# LEDs.net
KiCad netlist of a schematic drawn in Altium Designer
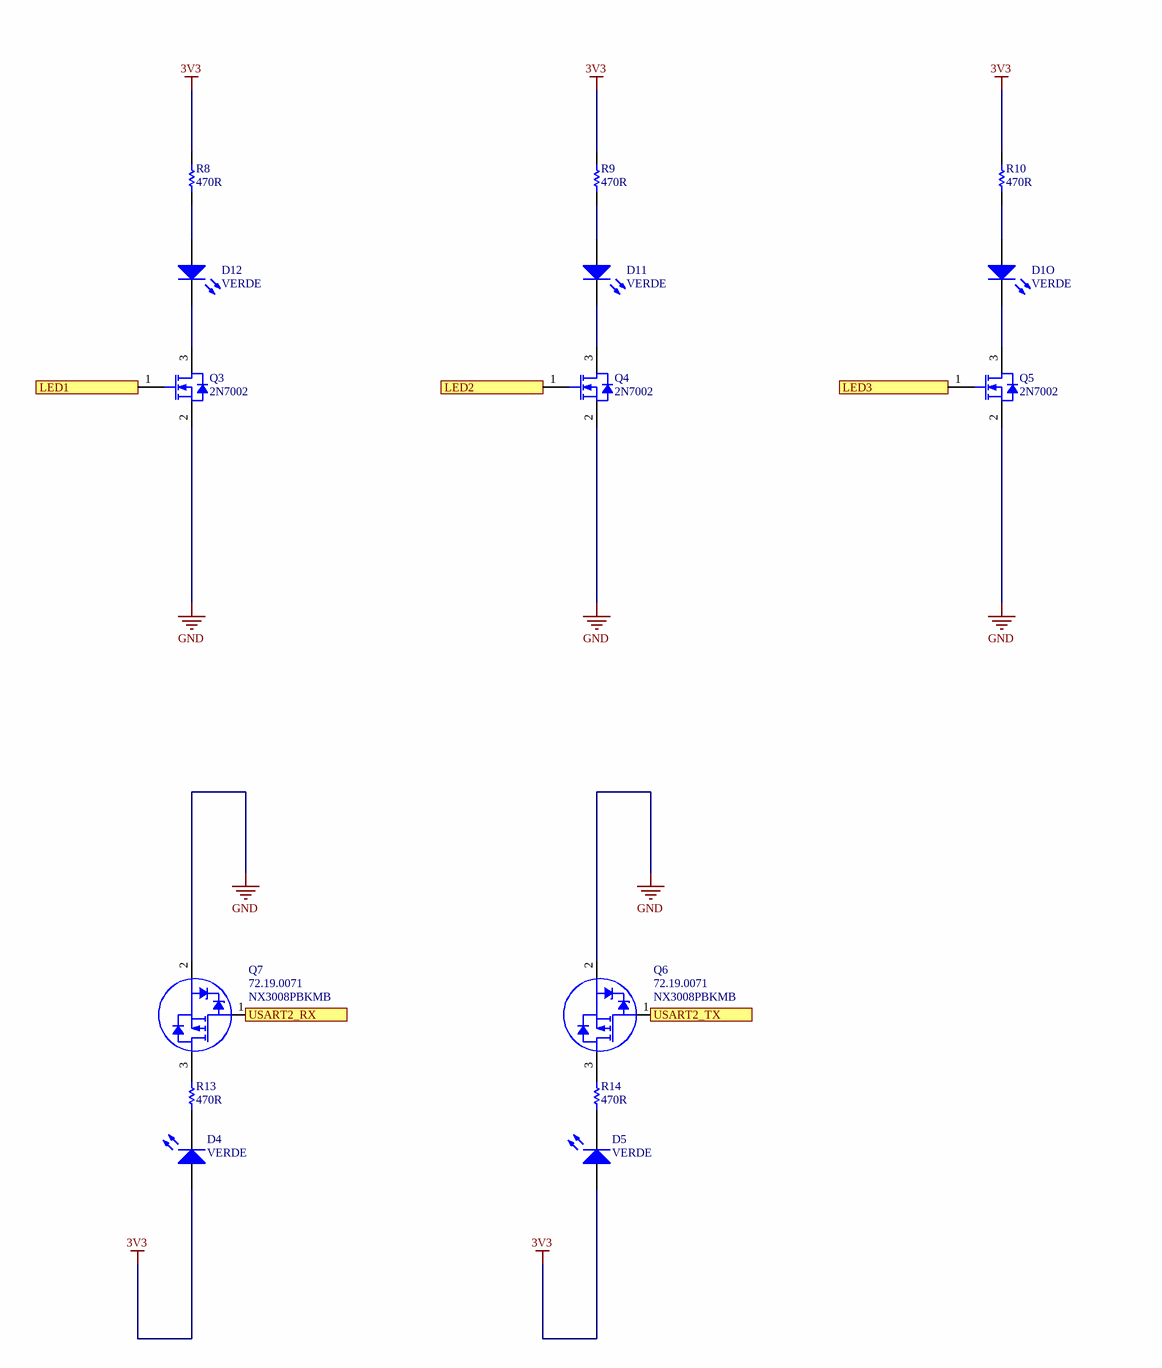
[diagram p0: LEDs.SchDoc, left]
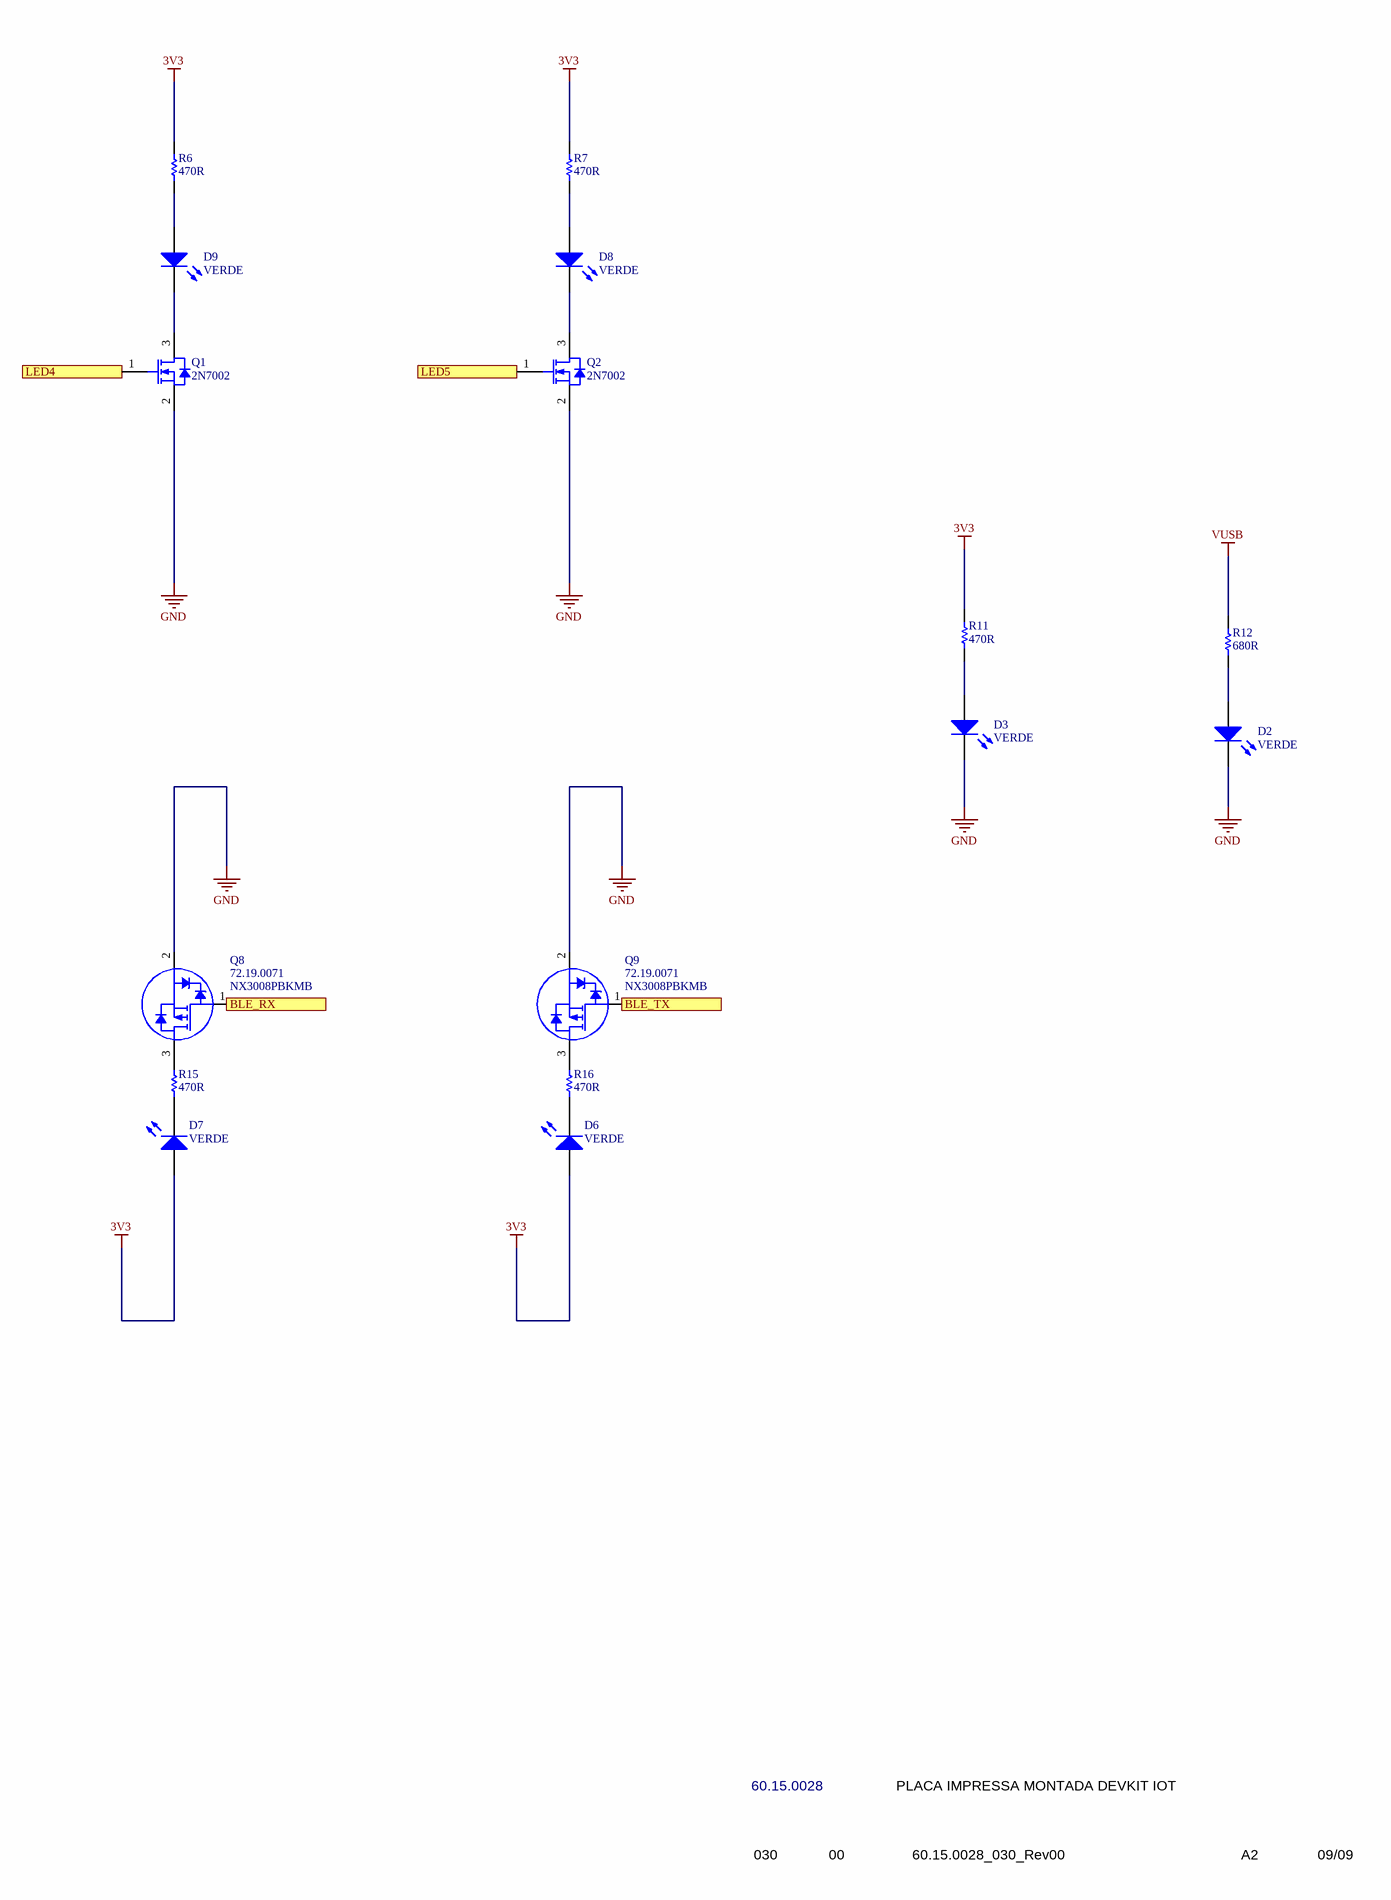
[diagram p1: LEDs.SchDoc, right]

(export (version "E")
  (design (tool "Eeschema 10.0.6"))
  (components
    (comp (ref "D1O")
      (value "32.17.0022")
      (footprint "32.17.0022")
      (description "LED VERDE SMD 20MA 5V")
      (fields (field (name "ALTIUM_UNNAMED_1") "VERDE"))
      (libsource (lib "OMNI-DIODOS_LED´s_DISPLAYS") (part "32.17.0022"))
    )
    (comp (ref "D2")
      (value "32.17.0022")
      (footprint "32.17.0022")
      (description "LED VERDE SMD 20MA 5V")
      (fields (field (name "ALTIUM_UNNAMED_1") "VERDE"))
      (libsource (lib "OMNI-DIODOS_LED´s_DISPLAYS") (part "32.17.0022"))
    )
    (comp (ref "D3")
      (value "32.17.0022")
      (footprint "32.17.0022")
      (description "LED VERDE SMD 20MA 5V")
      (fields (field (name "ALTIUM_UNNAMED_1") "VERDE"))
      (libsource (lib "OMNI-DIODOS_LED´s_DISPLAYS") (part "32.17.0022"))
    )
    (comp (ref "D4")
      (value "32.17.0022")
      (footprint "32.17.0022")
      (description "LED VERDE SMD 20MA 5V")
      (fields (field (name "ALTIUM_UNNAMED_1") "VERDE"))
      (libsource (lib "OMNI-DIODOS_LED´s_DISPLAYS") (part "32.17.0022"))
    )
    (comp (ref "D5")
      (value "32.17.0022")
      (footprint "32.17.0022")
      (description "LED VERDE SMD 20MA 5V")
      (fields (field (name "ALTIUM_UNNAMED_1") "VERDE"))
      (libsource (lib "OMNI-DIODOS_LED´s_DISPLAYS") (part "32.17.0022"))
    )
    (comp (ref "D6")
      (value "32.17.0022")
      (footprint "32.17.0022")
      (description "LED VERDE SMD 20MA 5V")
      (fields (field (name "ALTIUM_UNNAMED_1") "VERDE"))
      (libsource (lib "OMNI-DIODOS_LED´s_DISPLAYS") (part "32.17.0022"))
    )
    (comp (ref "D7")
      (value "32.17.0022")
      (footprint "32.17.0022")
      (description "LED VERDE SMD 20MA 5V")
      (fields (field (name "ALTIUM_UNNAMED_1") "VERDE"))
      (libsource (lib "OMNI-DIODOS_LED´s_DISPLAYS") (part "32.17.0022"))
    )
    (comp (ref "D8")
      (value "32.17.0022")
      (footprint "32.17.0022")
      (description "LED VERDE SMD 20MA 5V")
      (fields (field (name "ALTIUM_UNNAMED_1") "VERDE"))
      (libsource (lib "OMNI-DIODOS_LED´s_DISPLAYS") (part "32.17.0022"))
    )
    (comp (ref "D9")
      (value "32.17.0022")
      (footprint "32.17.0022")
      (description "LED VERDE SMD 20MA 5V")
      (fields (field (name "ALTIUM_UNNAMED_1") "VERDE"))
      (libsource (lib "OMNI-DIODOS_LED´s_DISPLAYS") (part "32.17.0022"))
    )
    (comp (ref "D11")
      (value "32.17.0022")
      (footprint "32.17.0022")
      (description "LED VERDE SMD 20MA 5V")
      (fields (field (name "ALTIUM_UNNAMED_1") "VERDE"))
      (libsource (lib "OMNI-DIODOS_LED´s_DISPLAYS") (part "32.17.0022"))
    )
    (comp (ref "D12")
      (value "32.17.0022")
      (footprint "32.17.0022")
      (description "LED VERDE SMD 20MA 5V")
      (fields (field (name "ALTIUM_UNNAMED_1") "VERDE"))
      (libsource (lib "OMNI-DIODOS_LED´s_DISPLAYS") (part "32.17.0022"))
    )
    (comp (ref "Q1")
      (value "72.19.0021")
      (footprint "72.19.0021")
      (description "TRANSISTOR MOSFET N 60V 115MA 0.2W SMD")
      (fields (field (name "ALTIUM_UNNAMED_1") "2N7002"))
      (libsource (lib "OMNI-TRANSISTORES") (part "72.19.0021"))
    )
    (comp (ref "Q2")
      (value "72.19.0021")
      (footprint "72.19.0021")
      (description "TRANSISTOR MOSFET N 60V 115MA 0.2W SMD")
      (fields (field (name "ALTIUM_UNNAMED_1") "2N7002"))
      (libsource (lib "OMNI-TRANSISTORES") (part "72.19.0021"))
    )
    (comp (ref "Q3")
      (value "72.19.0021")
      (footprint "72.19.0021")
      (description "TRANSISTOR MOSFET N 60V 115MA 0.2W SMD")
      (fields (field (name "ALTIUM_UNNAMED_1") "2N7002"))
      (libsource (lib "OMNI-TRANSISTORES") (part "72.19.0021"))
    )
    (comp (ref "Q4")
      (value "72.19.0021")
      (footprint "72.19.0021")
      (description "TRANSISTOR MOSFET N 60V 115MA 0.2W SMD")
      (fields (field (name "ALTIUM_UNNAMED_1") "2N7002"))
      (libsource (lib "OMNI-TRANSISTORES") (part "72.19.0021"))
    )
    (comp (ref "Q5")
      (value "72.19.0021")
      (footprint "72.19.0021")
      (description "TRANSISTOR MOSFET N 60V 115MA 0.2W SMD")
      (fields (field (name "ALTIUM_UNNAMED_1") "2N7002"))
      (libsource (lib "OMNI-TRANSISTORES") (part "72.19.0021"))
    )
    (comp (ref "Q6")
      (value "72.19.0071")
      (footprint "72.19.0071")
      (description "MOSFET CANAL P SMD 30V 230mA SOT883B")
      (fields (field (name "ALTIUM_UNNAMED_1") "NX3008PBKMB"))
      (libsource (lib "OMNI-TRANSISTORES") (part "72.19.0071"))
    )
    (comp (ref "Q7")
      (value "72.19.0071")
      (footprint "72.19.0071")
      (description "MOSFET CANAL P SMD 30V 230mA SOT883B")
      (fields (field (name "ALTIUM_UNNAMED_1") "NX3008PBKMB"))
      (libsource (lib "OMNI-TRANSISTORES") (part "72.19.0071"))
    )
    (comp (ref "Q8")
      (value "72.19.0071")
      (footprint "72.19.0071")
      (description "MOSFET CANAL P SMD 30V 230mA SOT883B")
      (fields (field (name "ALTIUM_UNNAMED_1") "NX3008PBKMB"))
      (libsource (lib "OMNI-TRANSISTORES") (part "72.19.0071"))
    )
    (comp (ref "Q9")
      (value "72.19.0071")
      (footprint "72.19.0071")
      (description "MOSFET CANAL P SMD 30V 230mA SOT883B")
      (fields (field (name "ALTIUM_UNNAMED_1") "NX3008PBKMB"))
      (libsource (lib "OMNI-TRANSISTORES") (part "72.19.0071"))
    )
    (comp (ref "R6")
      (value "470R")
      (footprint "66.33.4700")
      (description "RES MET 0,125W 470 OHMS 5% SMD 0805")
      (fields (field (name "Comment") "66.33.4700"))
      (libsource (lib "OMNI-RESISTORES") (part "66.33.4700"))
    )
    (comp (ref "R7")
      (value "470R")
      (footprint "66.33.4700")
      (description "RES MET 0,125W 470 OHMS 5% SMD 0805")
      (fields (field (name "Comment") "66.33.4700"))
      (libsource (lib "OMNI-RESISTORES") (part "66.33.4700"))
    )
    (comp (ref "R8")
      (value "470R")
      (footprint "66.33.4700")
      (description "RES MET 0,125W 470 OHMS 5% SMD 0805")
      (fields (field (name "Comment") "66.33.4700"))
      (libsource (lib "OMNI-RESISTORES") (part "66.33.4700"))
    )
    (comp (ref "R9")
      (value "470R")
      (footprint "66.33.4700")
      (description "RES MET 0,125W 470 OHMS 5% SMD 0805")
      (fields (field (name "Comment") "66.33.4700"))
      (libsource (lib "OMNI-RESISTORES") (part "66.33.4700"))
    )
    (comp (ref "R10")
      (value "470R")
      (footprint "66.33.4700")
      (description "RES MET 0,125W 470 OHMS 5% SMD 0805")
      (fields (field (name "Comment") "66.33.4700"))
      (libsource (lib "OMNI-RESISTORES") (part "66.33.4700"))
    )
    (comp (ref "R11")
      (value "470R")
      (footprint "66.33.4700")
      (description "RES MET 0,125W 470 OHMS 5% SMD 0805")
      (fields (field (name "Comment") "66.33.4700"))
      (libsource (lib "OMNI-RESISTORES") (part "66.33.4700"))
    )
    (comp (ref "R12")
      (value "680R")
      (footprint "66.33.6800")
      (description "RES MET 0,125W 680 OHMS 5% SMD 0805")
      (fields (field (name "Comment") "66.33.6800"))
      (libsource (lib "OMNI-RESISTORES") (part "66.33.6800"))
    )
    (comp (ref "R13")
      (value "470R")
      (footprint "66.33.4700")
      (description "RES MET 0,125W 470 OHMS 5% SMD 0805")
      (fields (field (name "Comment") "66.33.4700"))
      (libsource (lib "OMNI-RESISTORES") (part "66.33.4700"))
    )
    (comp (ref "R14")
      (value "470R")
      (footprint "66.33.4700")
      (description "RES MET 0,125W 470 OHMS 5% SMD 0805")
      (fields (field (name "Comment") "66.33.4700"))
      (libsource (lib "OMNI-RESISTORES") (part "66.33.4700"))
    )
    (comp (ref "R15")
      (value "470R")
      (footprint "66.33.4700")
      (description "RES MET 0,125W 470 OHMS 5% SMD 0805")
      (fields (field (name "Comment") "66.33.4700"))
      (libsource (lib "OMNI-RESISTORES") (part "66.33.4700"))
    )
    (comp (ref "R16")
      (value "470R")
      (footprint "66.33.4700")
      (description "RES MET 0,125W 470 OHMS 5% SMD 0805")
      (fields (field (name "Comment") "66.33.4700"))
      (libsource (lib "OMNI-RESISTORES") (part "66.33.4700"))
    )
  )
  (nets
    (net (code "1") (name "/BLE_RX") (class "Default")
      (node (ref "Q8") (pin "1") (pinfunction "G_1") (pintype "passive"))
    )
    (net (code "2") (name "/BLE_TX") (class "Default")
      (node (ref "Q9") (pin "1") (pinfunction "G_1") (pintype "passive"))
    )
    (net (code "3") (name "/LED1") (class "Default")
      (node (ref "Q3") (pin "1") (pinfunction "G_1") (pintype "passive"))
    )
    (net (code "4") (name "/LED2") (class "Default")
      (node (ref "Q4") (pin "1") (pinfunction "G_1") (pintype "passive"))
    )
    (net (code "5") (name "/LED3") (class "Default")
      (node (ref "Q5") (pin "1") (pinfunction "G_1") (pintype "passive"))
    )
    (net (code "6") (name "/LED4") (class "Default")
      (node (ref "Q1") (pin "1") (pinfunction "G_1") (pintype "passive"))
    )
    (net (code "7") (name "/LED5") (class "Default")
      (node (ref "Q2") (pin "1") (pinfunction "G_1") (pintype "passive"))
    )
    (net (code "8") (name "/USART2_RX") (class "Default")
      (node (ref "Q7") (pin "1") (pinfunction "G_1") (pintype "passive"))
    )
    (net (code "9") (name "/USART2_TX") (class "Default")
      (node (ref "Q6") (pin "1") (pinfunction "G_1") (pintype "passive"))
    )
    (net (code "10") (name "3V3") (class "Default")
      (node (ref "D4") (pin "A") (pinfunction "A_A") (pintype "passive"))
      (node (ref "D5") (pin "A") (pinfunction "A_A") (pintype "passive"))
      (node (ref "D6") (pin "A") (pinfunction "A_A") (pintype "passive"))
      (node (ref "D7") (pin "A") (pinfunction "A_A") (pintype "passive"))
      (node (ref "R10") (pin "2") (pinfunction "2_2") (pintype "passive"))
      (node (ref "R11") (pin "2") (pinfunction "2_2") (pintype "passive"))
      (node (ref "R6") (pin "2") (pinfunction "2_2") (pintype "passive"))
      (node (ref "R7") (pin "2") (pinfunction "2_2") (pintype "passive"))
      (node (ref "R8") (pin "2") (pinfunction "2_2") (pintype "passive"))
      (node (ref "R9") (pin "2") (pinfunction "2_2") (pintype "passive"))
    )
    (net (code "11") (name "GND") (class "Default")
      (node (ref "D2") (pin "K") (pinfunction "K_K") (pintype "passive"))
      (node (ref "D3") (pin "K") (pinfunction "K_K") (pintype "passive"))
      (node (ref "Q1") (pin "2") (pinfunction "S_2") (pintype "passive"))
      (node (ref "Q2") (pin "2") (pinfunction "S_2") (pintype "passive"))
      (node (ref "Q3") (pin "2") (pinfunction "S_2") (pintype "passive"))
      (node (ref "Q4") (pin "2") (pinfunction "S_2") (pintype "passive"))
      (node (ref "Q5") (pin "2") (pinfunction "S_2") (pintype "passive"))
      (node (ref "Q6") (pin "2") (pinfunction "S_2") (pintype "passive"))
      (node (ref "Q7") (pin "2") (pinfunction "S_2") (pintype "passive"))
      (node (ref "Q8") (pin "2") (pinfunction "S_2") (pintype "passive"))
      (node (ref "Q9") (pin "2") (pinfunction "S_2") (pintype "passive"))
    )
    (net (code "12") (name "Net-(D1O-PadA)") (class "Default")
      (node (ref "D1O") (pin "A") (pinfunction "A_A") (pintype "passive"))
      (node (ref "R10") (pin "1") (pinfunction "1_1") (pintype "passive"))
    )
    (net (code "13") (name "Net-(D2-PadA)") (class "Default")
      (node (ref "D2") (pin "A") (pinfunction "A_A") (pintype "passive"))
      (node (ref "R12") (pin "1") (pinfunction "1_1") (pintype "passive"))
    )
    (net (code "14") (name "Net-(D3-PadA)") (class "Default")
      (node (ref "D3") (pin "A") (pinfunction "A_A") (pintype "passive"))
      (node (ref "R11") (pin "1") (pinfunction "1_1") (pintype "passive"))
    )
    (net (code "15") (name "Net-(D4-PadK)") (class "Default")
      (node (ref "D4") (pin "K") (pinfunction "K_K") (pintype "passive"))
      (node (ref "R13") (pin "1") (pinfunction "1_1") (pintype "passive"))
    )
    (net (code "16") (name "Net-(D5-PadK)") (class "Default")
      (node (ref "D5") (pin "K") (pinfunction "K_K") (pintype "passive"))
      (node (ref "R14") (pin "1") (pinfunction "1_1") (pintype "passive"))
    )
    (net (code "17") (name "Net-(D6-PadK)") (class "Default")
      (node (ref "D6") (pin "K") (pinfunction "K_K") (pintype "passive"))
      (node (ref "R16") (pin "1") (pinfunction "1_1") (pintype "passive"))
    )
    (net (code "18") (name "Net-(D7-PadK)") (class "Default")
      (node (ref "D7") (pin "K") (pinfunction "K_K") (pintype "passive"))
      (node (ref "R15") (pin "1") (pinfunction "1_1") (pintype "passive"))
    )
    (net (code "19") (name "Net-(D8-PadA)") (class "Default")
      (node (ref "D8") (pin "A") (pinfunction "A_A") (pintype "passive"))
      (node (ref "R7") (pin "1") (pinfunction "1_1") (pintype "passive"))
    )
    (net (code "20") (name "Net-(D9-PadA)") (class "Default")
      (node (ref "D9") (pin "A") (pinfunction "A_A") (pintype "passive"))
      (node (ref "R6") (pin "1") (pinfunction "1_1") (pintype "passive"))
    )
    (net (code "21") (name "Net-(D11-PadA)") (class "Default")
      (node (ref "D11") (pin "A") (pinfunction "A_A") (pintype "passive"))
      (node (ref "R9") (pin "1") (pinfunction "1_1") (pintype "passive"))
    )
    (net (code "22") (name "Net-(D12-PadA)") (class "Default")
      (node (ref "D12") (pin "A") (pinfunction "A_A") (pintype "passive"))
      (node (ref "R8") (pin "1") (pinfunction "1_1") (pintype "passive"))
    )
    (net (code "23") (name "Net-(Q1-D)") (class "Default")
      (node (ref "D9") (pin "K") (pinfunction "K_K") (pintype "passive"))
      (node (ref "Q1") (pin "3") (pinfunction "D_3") (pintype "passive"))
    )
    (net (code "24") (name "Net-(Q2-D)") (class "Default")
      (node (ref "D8") (pin "K") (pinfunction "K_K") (pintype "passive"))
      (node (ref "Q2") (pin "3") (pinfunction "D_3") (pintype "passive"))
    )
    (net (code "25") (name "Net-(Q3-D)") (class "Default")
      (node (ref "D12") (pin "K") (pinfunction "K_K") (pintype "passive"))
      (node (ref "Q3") (pin "3") (pinfunction "D_3") (pintype "passive"))
    )
    (net (code "26") (name "Net-(Q4-D)") (class "Default")
      (node (ref "D11") (pin "K") (pinfunction "K_K") (pintype "passive"))
      (node (ref "Q4") (pin "3") (pinfunction "D_3") (pintype "passive"))
    )
    (net (code "27") (name "Net-(Q5-D)") (class "Default")
      (node (ref "D1O") (pin "K") (pinfunction "K_K") (pintype "passive"))
      (node (ref "Q5") (pin "3") (pinfunction "D_3") (pintype "passive"))
    )
    (net (code "28") (name "Net-(Q6-D)") (class "Default")
      (node (ref "Q6") (pin "3") (pinfunction "D_3") (pintype "passive"))
      (node (ref "R14") (pin "2") (pinfunction "2_2") (pintype "passive"))
    )
    (net (code "29") (name "Net-(Q7-D)") (class "Default")
      (node (ref "Q7") (pin "3") (pinfunction "D_3") (pintype "passive"))
      (node (ref "R13") (pin "2") (pinfunction "2_2") (pintype "passive"))
    )
    (net (code "30") (name "Net-(Q8-D)") (class "Default")
      (node (ref "Q8") (pin "3") (pinfunction "D_3") (pintype "passive"))
      (node (ref "R15") (pin "2") (pinfunction "2_2") (pintype "passive"))
    )
    (net (code "31") (name "Net-(Q9-D)") (class "Default")
      (node (ref "Q9") (pin "3") (pinfunction "D_3") (pintype "passive"))
      (node (ref "R16") (pin "2") (pinfunction "2_2") (pintype "passive"))
    )
    (net (code "32") (name "VUSB") (class "Default")
      (node (ref "R12") (pin "2") (pinfunction "2_2") (pintype "passive"))
    )
  )
)
